# rambo_e2p.net
KiCad netlist of a schematic drawn in EAGLE
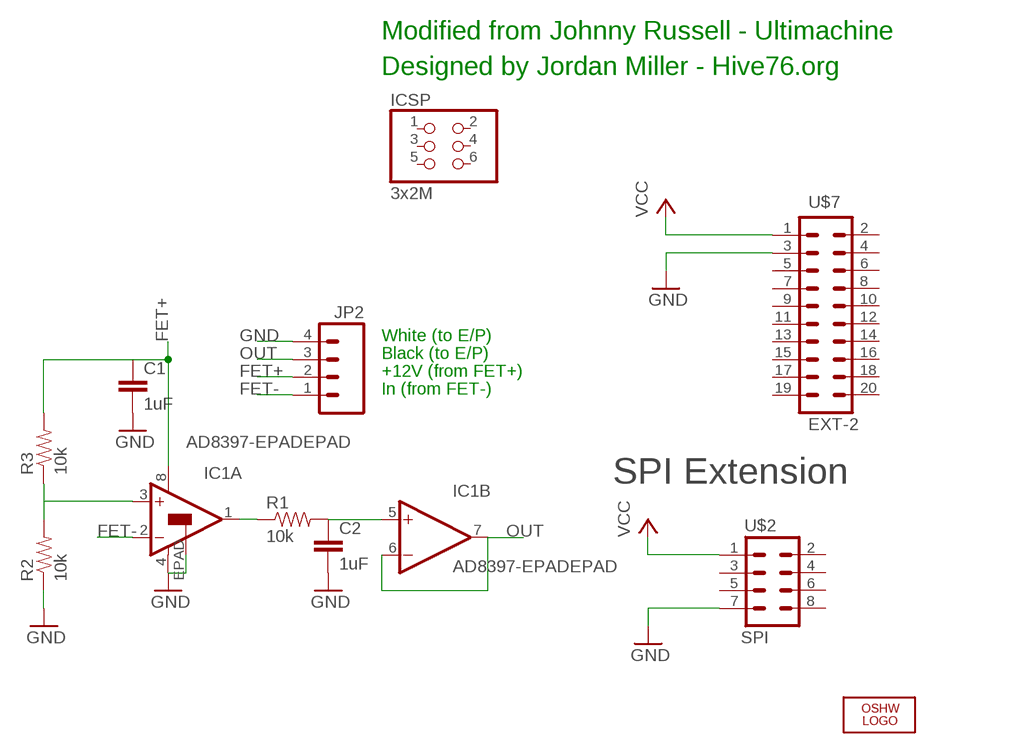
[diagram p0: schematic, sheet 1]

(export (version "E")
  (design (tool "Eeschema 10.0.6"))
  (components
    (comp (ref "C1")
      (value "1uF")
      (footprint "eagle-import:0805")
      (libsource (lib "eagle-import") (part "1UF-25V-10%(0805)"))
    )
    (comp (ref "C2")
      (value "1uF")
      (footprint "eagle-import:0805")
      (fields (field (name "PROD_ID") "CAP-08064"))
      (libsource (lib "eagle-import") (part "1UF-25V-10%(0805)"))
    )
    (comp (ref "IC1")
      (value "AD8397-EPADEPAD")
      (footprint "eagle-import:SO08-EPAD")
      (libsource (lib "eagle-import") (part "AD8397-EPADEPAD"))
    )
    (comp (ref "ICSP")
      (value "3x2M")
      (footprint "eagle-import:2X03")
      (libsource (lib "eagle-import") (part "PINHD-2X3"))
    )
    (comp (ref "JP2")
      (value "M04SCREW")
      (footprint "eagle-import:SCREWTERMINAL-3.5MM-4")
      (libsource (lib "eagle-import") (part "M04SCREW"))
    )
    (comp (ref "LOGO1")
      (value "OSHW_LOGO_8MILX0150-NT")
      (footprint "eagle-import:OSHW_8X150_NOTEXT")
      (libsource (lib "eagle-import") (part "OSHW_LOGO_8MILX0150-NT"))
    )
    (comp (ref "R1")
      (value "10k")
      (footprint "eagle-import:0805")
      (libsource (lib "eagle-import") (part "RESISTOR0805-RES"))
    )
    (comp (ref "R2")
      (value "10k")
      (footprint "eagle-import:0805")
      (libsource (lib "eagle-import") (part "RESISTOR0805-RES"))
    )
    (comp (ref "R3")
      (value "10k")
      (footprint "eagle-import:0805")
      (libsource (lib "eagle-import") (part "RESISTOR0805-RES"))
    )
    (comp (ref "U$2")
      (value "SPI")
      (footprint "eagle-import:2X4")
      (libsource (lib "eagle-import") (part "M04X2"))
    )
    (comp (ref "U$7")
      (value "EXT-2")
      (footprint "eagle-import:2X10")
      (libsource (lib "eagle-import") (part "M10X2"))
    )
  )
  (nets
    (net (code "1") (name "/FET+") (class "Default")
      (node (ref "C1") (pin "1") (pinfunction "1_1") (pintype "passive"))
      (node (ref "IC1") (pin "8") (pinfunction "V+_8") (pintype "power_in"))
      (node (ref "JP2") (pin "2") (pinfunction "2_2") (pintype "passive"))
      (node (ref "R3") (pin "2") (pinfunction "2_2") (pintype "passive"))
    )
    (net (code "2") (name "/FET-") (class "Default")
      (node (ref "IC1") (pin "2") (pinfunction "-IN_2") (pintype "input"))
      (node (ref "JP2") (pin "1") (pinfunction "1_1") (pintype "passive"))
    )
    (net (code "3") (name "/OUT") (class "Default")
      (node (ref "IC1") (pin "6") (pinfunction "-IN_6") (pintype "input"))
      (node (ref "IC1") (pin "7") (pinfunction "OUT_7") (pintype "output"))
      (node (ref "JP2") (pin "3") (pinfunction "3_3") (pintype "passive"))
    )
    (net (code "4") (name "GND") (class "Default")
      (node (ref "C1") (pin "2") (pinfunction "2_2") (pintype "passive"))
      (node (ref "C2") (pin "2") (pinfunction "2_2") (pintype "passive"))
      (node (ref "IC1") (pin "4") (pinfunction "V-_4") (pintype "power_in"))
      (node (ref "IC1") (pin "EPAD") (pinfunction "EPAD_EPAD") (pintype "bidirectional"))
      (node (ref "JP2") (pin "4") (pinfunction "4_4") (pintype "passive"))
      (node (ref "R2") (pin "1") (pinfunction "1_1") (pintype "passive"))
      (node (ref "U$2") (pin "7") (pinfunction "7_7") (pintype "passive"))
      (node (ref "U$7") (pin "3") (pinfunction "3_3") (pintype "passive"))
    )
    (net (code "5") (name "Net-(IC1A-+IN)") (class "Default")
      (node (ref "IC1") (pin "3") (pinfunction "+IN_3") (pintype "input"))
      (node (ref "R2") (pin "2") (pinfunction "2_2") (pintype "passive"))
      (node (ref "R3") (pin "1") (pinfunction "1_1") (pintype "passive"))
    )
    (net (code "6") (name "Net-(IC1A-OUT)") (class "Default")
      (node (ref "IC1") (pin "1") (pinfunction "OUT_1") (pintype "output"))
      (node (ref "R1") (pin "1") (pinfunction "1_1") (pintype "passive"))
    )
    (net (code "7") (name "Net-(IC1B-+IN)") (class "Default")
      (node (ref "C2") (pin "1") (pinfunction "1_1") (pintype "passive"))
      (node (ref "IC1") (pin "5") (pinfunction "+IN_5") (pintype "input"))
      (node (ref "R1") (pin "2") (pinfunction "2_2") (pintype "passive"))
    )
    (net (code "8") (name "VCC") (class "Default")
      (node (ref "U$2") (pin "1") (pinfunction "1_1") (pintype "passive"))
      (node (ref "U$7") (pin "1") (pinfunction "1_1") (pintype "passive"))
    )
    (net (code "9") (name "unconnected-(ICSP-Pad1)") (class "Default")
      (node (ref "ICSP") (pin "1") (pinfunction "1_1") (pintype "passive"))
    )
    (net (code "10") (name "unconnected-(ICSP-Pad2)") (class "Default")
      (node (ref "ICSP") (pin "2") (pinfunction "2_2") (pintype "passive"))
    )
    (net (code "11") (name "unconnected-(ICSP-Pad3)") (class "Default")
      (node (ref "ICSP") (pin "3") (pinfunction "3_3") (pintype "passive"))
    )
    (net (code "12") (name "unconnected-(ICSP-Pad4)") (class "Default")
      (node (ref "ICSP") (pin "4") (pinfunction "4_4") (pintype "passive"))
    )
    (net (code "13") (name "unconnected-(ICSP-Pad5)") (class "Default")
      (node (ref "ICSP") (pin "5") (pinfunction "5_5") (pintype "passive"))
    )
    (net (code "14") (name "unconnected-(ICSP-Pad6)") (class "Default")
      (node (ref "ICSP") (pin "6") (pinfunction "6_6") (pintype "passive"))
    )
    (net (code "15") (name "unconnected-(U$2-Pad2)") (class "Default")
      (node (ref "U$2") (pin "2") (pinfunction "2_2") (pintype "passive"))
    )
    (net (code "16") (name "unconnected-(U$2-Pad3)") (class "Default")
      (node (ref "U$2") (pin "3") (pinfunction "3_3") (pintype "passive"))
    )
    (net (code "17") (name "unconnected-(U$2-Pad4)") (class "Default")
      (node (ref "U$2") (pin "4") (pinfunction "4_4") (pintype "passive"))
    )
    (net (code "18") (name "unconnected-(U$2-Pad5)") (class "Default")
      (node (ref "U$2") (pin "5") (pinfunction "5_5") (pintype "passive"))
    )
    (net (code "19") (name "unconnected-(U$2-Pad6)") (class "Default")
      (node (ref "U$2") (pin "6") (pinfunction "6_6") (pintype "passive"))
    )
    (net (code "20") (name "unconnected-(U$2-Pad8)") (class "Default")
      (node (ref "U$2") (pin "8") (pinfunction "8_8") (pintype "passive"))
    )
    (net (code "21") (name "unconnected-(U$7-Pad2)") (class "Default")
      (node (ref "U$7") (pin "2") (pinfunction "2_2") (pintype "passive"))
    )
    (net (code "22") (name "unconnected-(U$7-Pad4)") (class "Default")
      (node (ref "U$7") (pin "4") (pinfunction "4_4") (pintype "passive"))
    )
    (net (code "23") (name "unconnected-(U$7-Pad5)") (class "Default")
      (node (ref "U$7") (pin "5") (pinfunction "5_5") (pintype "passive"))
    )
    (net (code "24") (name "unconnected-(U$7-Pad6)") (class "Default")
      (node (ref "U$7") (pin "6") (pinfunction "6_6") (pintype "passive"))
    )
    (net (code "25") (name "unconnected-(U$7-Pad7)") (class "Default")
      (node (ref "U$7") (pin "7") (pinfunction "7_7") (pintype "passive"))
    )
    (net (code "26") (name "unconnected-(U$7-Pad8)") (class "Default")
      (node (ref "U$7") (pin "8") (pinfunction "8_8") (pintype "passive"))
    )
    (net (code "27") (name "unconnected-(U$7-Pad9)") (class "Default")
      (node (ref "U$7") (pin "9") (pinfunction "9_9") (pintype "passive"))
    )
    (net (code "28") (name "unconnected-(U$7-Pad10)") (class "Default")
      (node (ref "U$7") (pin "10") (pinfunction "10_10") (pintype "passive"))
    )
    (net (code "29") (name "unconnected-(U$7-Pad11)") (class "Default")
      (node (ref "U$7") (pin "11") (pinfunction "11_11") (pintype "passive"))
    )
    (net (code "30") (name "unconnected-(U$7-Pad12)") (class "Default")
      (node (ref "U$7") (pin "12") (pinfunction "12_12") (pintype "passive"))
    )
    (net (code "31") (name "unconnected-(U$7-Pad13)") (class "Default")
      (node (ref "U$7") (pin "13") (pinfunction "13_13") (pintype "passive"))
    )
    (net (code "32") (name "unconnected-(U$7-Pad14)") (class "Default")
      (node (ref "U$7") (pin "14") (pinfunction "14_14") (pintype "passive"))
    )
    (net (code "33") (name "unconnected-(U$7-Pad15)") (class "Default")
      (node (ref "U$7") (pin "15") (pinfunction "15_15") (pintype "passive"))
    )
    (net (code "34") (name "unconnected-(U$7-Pad16)") (class "Default")
      (node (ref "U$7") (pin "16") (pinfunction "16_16") (pintype "passive"))
    )
    (net (code "35") (name "unconnected-(U$7-Pad17)") (class "Default")
      (node (ref "U$7") (pin "17") (pinfunction "17_17") (pintype "passive"))
    )
    (net (code "36") (name "unconnected-(U$7-Pad18)") (class "Default")
      (node (ref "U$7") (pin "18") (pinfunction "18_18") (pintype "passive"))
    )
    (net (code "37") (name "unconnected-(U$7-Pad19)") (class "Default")
      (node (ref "U$7") (pin "19") (pinfunction "19_19") (pintype "passive"))
    )
    (net (code "38") (name "unconnected-(U$7-Pad20)") (class "Default")
      (node (ref "U$7") (pin "20") (pinfunction "20_20") (pintype "passive"))
    )
  )
)
